# BUCK_CONVERTERS.net
KiCad netlist of a schematic drawn in Altium Designer
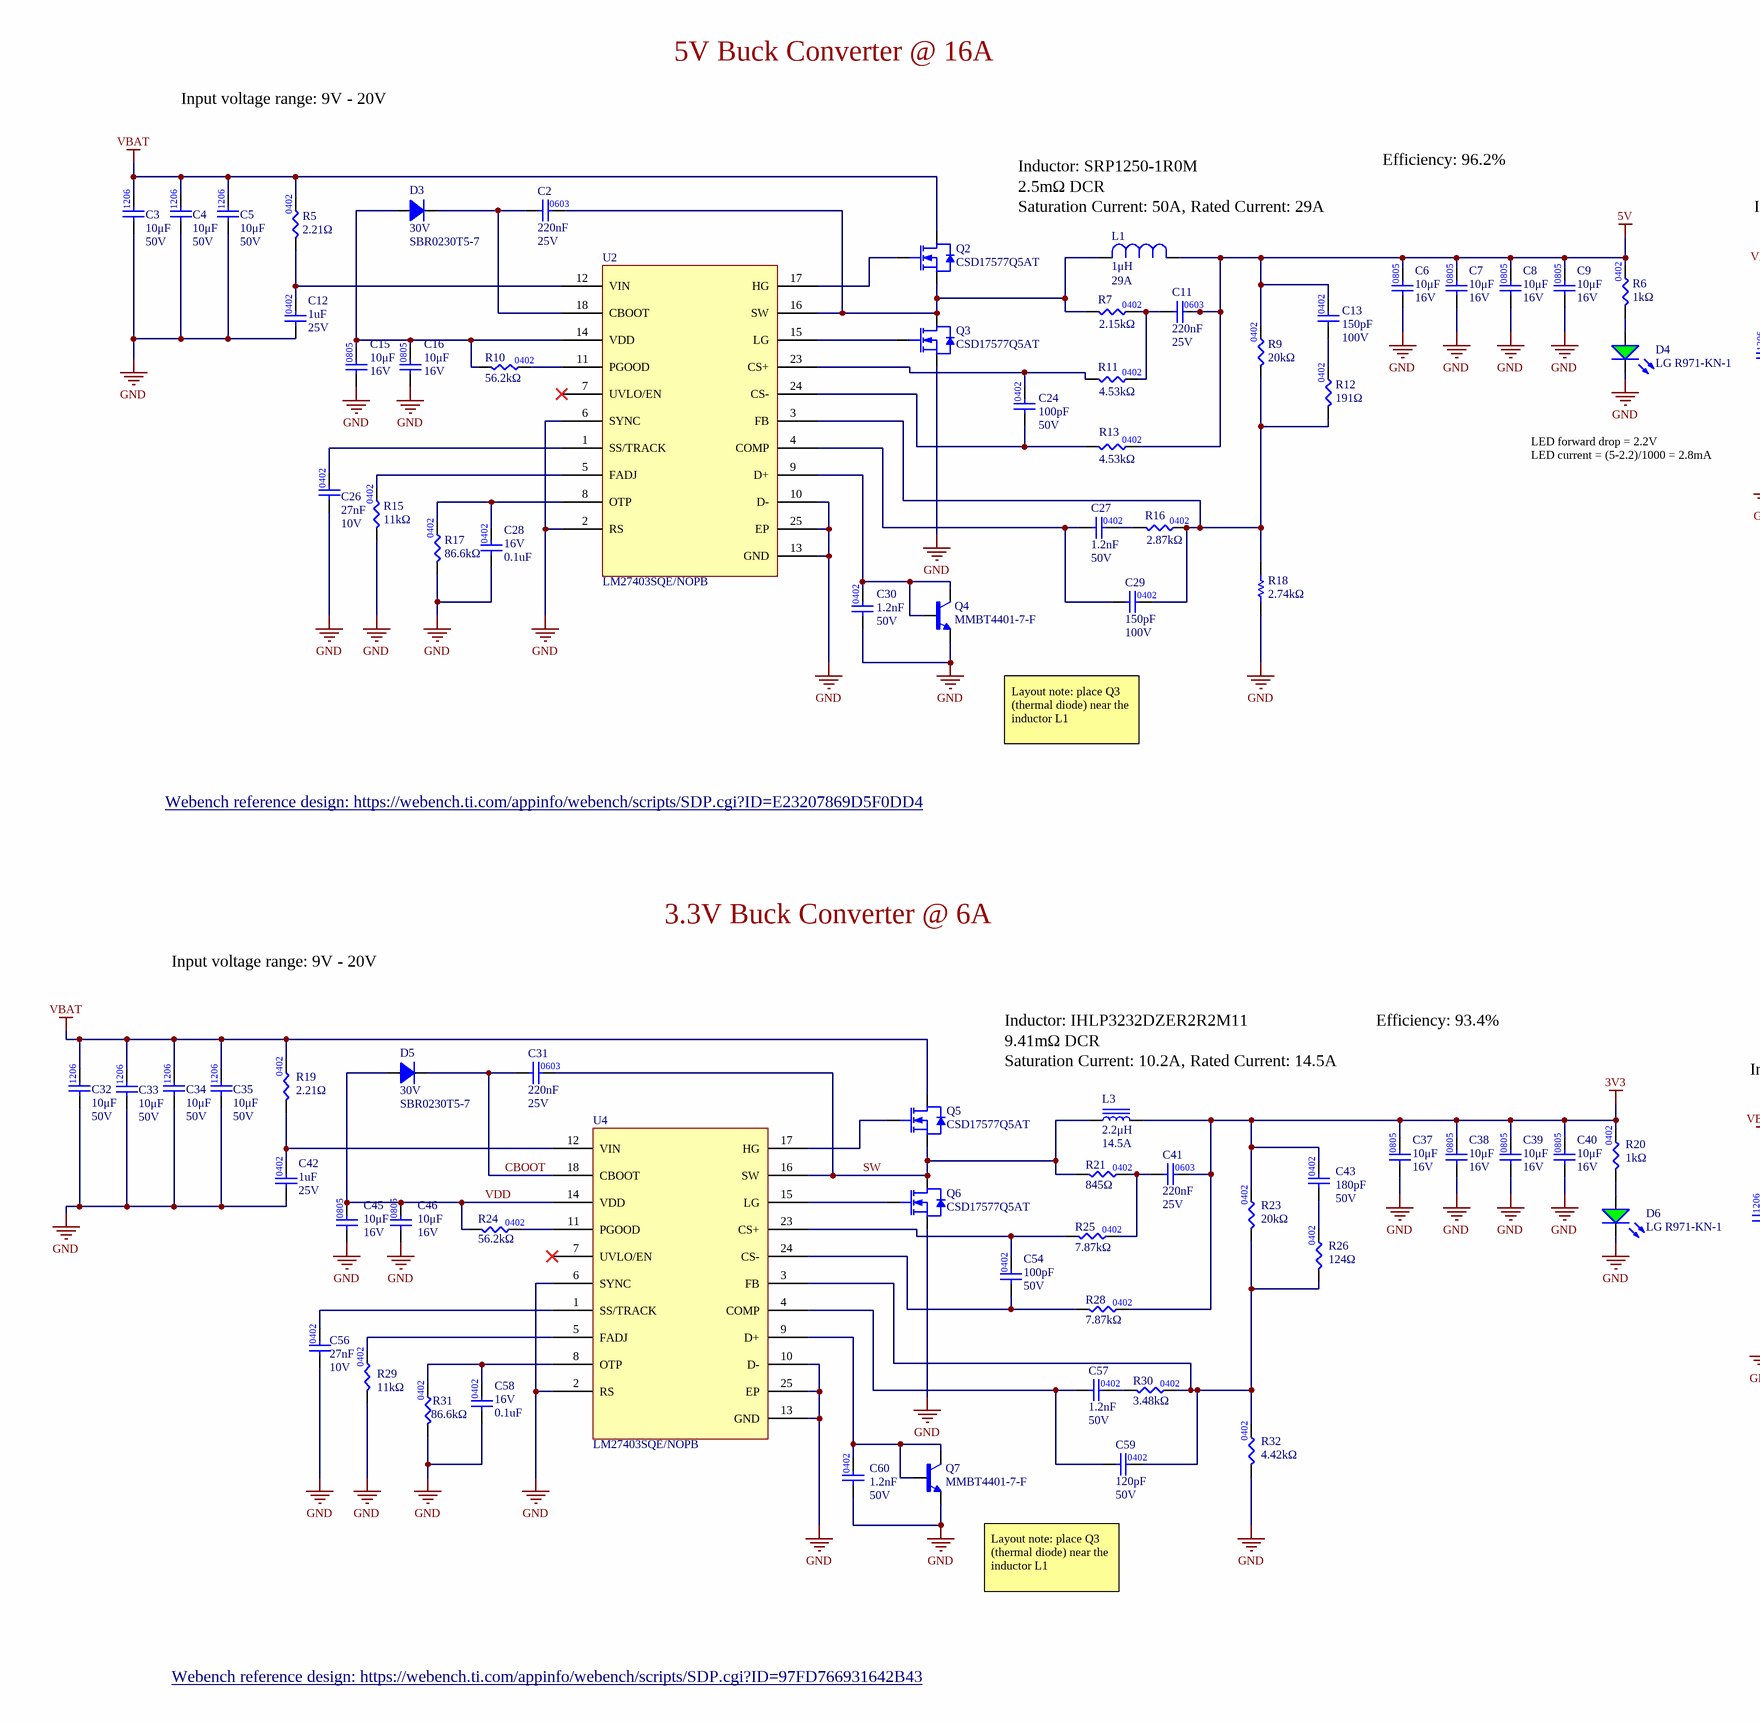
[diagram p0: BUCK CONVERTERS.SchDoc, left]
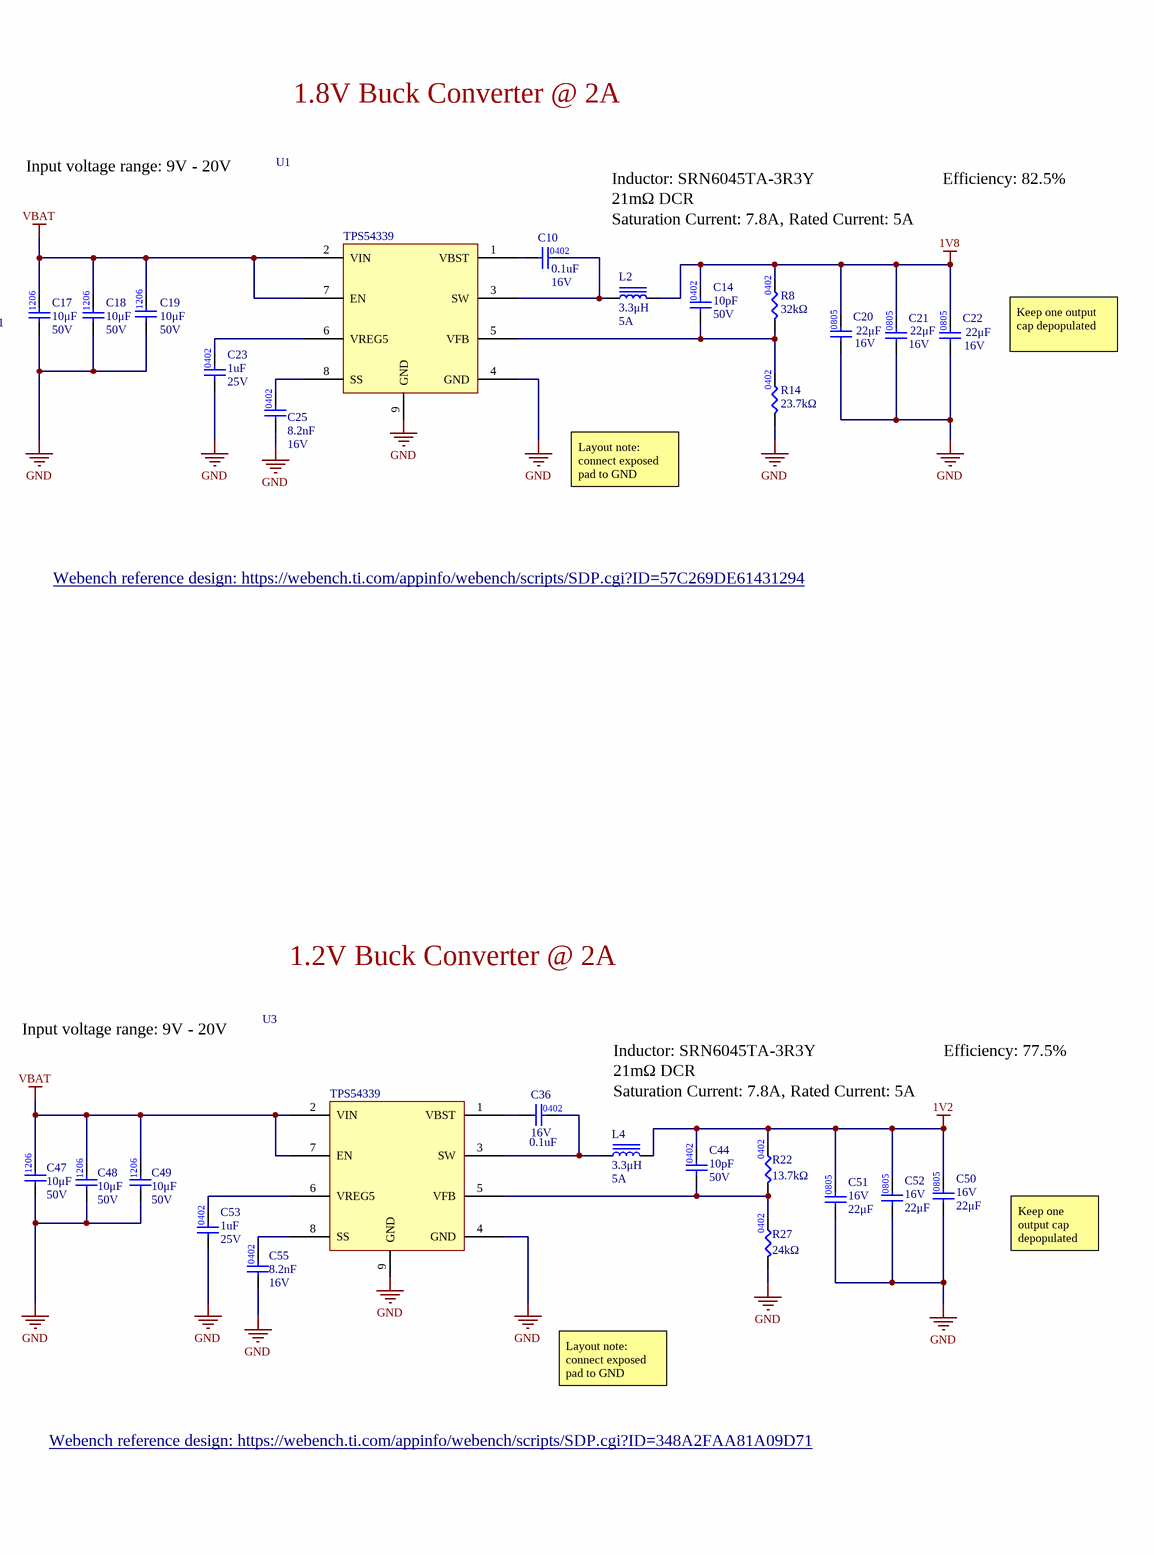
[diagram p1: BUCK CONVERTERS.SchDoc, right]

(export (version "E")
  (design (tool "Eeschema 10.0.6"))
  (components
    (comp (ref "C2")
      (value "CAP_0.22uF_25V_X5R_0402")
      (footprint "CAP0402")
      (description "0.22 µF ±10% 25V Ceramic Capacitor X5R 0402 (1005 Metric)")
      (fields
        (field (name "MANUFACTURER") "Yageo")
        (field (name "MANUFACTURER PART NUMBER") "CC0402KRX5R8BB224")
        (field (name "CAPACITANCE") "220nF")
        (field (name "RATED DC VOLTAGE (URDC)") "25V")
      )
      (libsource (lib "UWRT_Schematic_Library_2020") (part "CAP_0.22uF_25V_X5R_0402"))
    )
    (comp (ref "C3")
      (value "10μF")
      (footprint "CAP1210")
      (description "CAP CER 10UF 50V X7R 1210")
      (fields (field (name "VOLTAGE RATING") "50V") (field (name "Comment") "CAP_10uF_50V_1210"))
      (libsource (lib "UWRT_Schematic_Library_2020") (part "CAP_10uF_50V_1210"))
    )
    (comp (ref "C4")
      (value "10μF")
      (footprint "CAP1210")
      (description "CAP CER 10UF 50V X7R 1210")
      (fields (field (name "VOLTAGE RATING") "50V") (field (name "Comment") "CAP_10uF_50V_1210"))
      (libsource (lib "UWRT_Schematic_Library_2020") (part "CAP_10uF_50V_1210"))
    )
    (comp (ref "C5")
      (value "10μF")
      (footprint "CAP1210")
      (description "CAP CER 10UF 50V X7R 1210")
      (fields (field (name "VOLTAGE RATING") "50V") (field (name "Comment") "CAP_10uF_50V_1210"))
      (libsource (lib "UWRT_Schematic_Library_2020") (part "CAP_10uF_50V_1210"))
    )
    (comp (ref "C6")
      (value "10μF")
      (footprint "CAP2012")
      (description "CAP CER 10UF 16V X5R 0805")
      (fields (field (name "VOLTAGE RATING") "16V") (field (name "Comment") "CAP_10uF_16V_0805"))
      (libsource (lib "UWRT_Schematic_Library_2020") (part "CAP_10uF_16V_0805"))
    )
    (comp (ref "C7")
      (value "10μF")
      (footprint "CAP2012")
      (description "CAP CER 10UF 16V X5R 0805")
      (fields (field (name "VOLTAGE RATING") "16V") (field (name "Comment") "CAP_10uF_16V_0805"))
      (libsource (lib "UWRT_Schematic_Library_2020") (part "CAP_10uF_16V_0805"))
    )
    (comp (ref "C8")
      (value "10μF")
      (footprint "CAP2012")
      (description "CAP CER 10UF 16V X5R 0805")
      (fields (field (name "VOLTAGE RATING") "16V") (field (name "Comment") "CAP_10uF_16V_0805"))
      (libsource (lib "UWRT_Schematic_Library_2020") (part "CAP_10uF_16V_0805"))
    )
    (comp (ref "C9")
      (value "10μF")
      (footprint "CAP2012")
      (description "CAP CER 10UF 16V X5R 0805")
      (fields (field (name "VOLTAGE RATING") "16V") (field (name "Comment") "CAP_10uF_16V_0805"))
      (libsource (lib "UWRT_Schematic_Library_2020") (part "CAP_10uF_16V_0805"))
    )
    (comp (ref "C10")
      (value "CAP_0.1uF_16V_X7R_0402")
      (footprint "CAP0402")
      (description "Ceramic Capacitor, Ceramic")
      (fields
        (field (name "MANUFACTURER") "Taiyo Yuden")
        (field (name "MANUFACTURER PART NUMBER") "LMK212AC6106MD-T")
        (field (name "RATED DC VOLTAGE (URDC)") "16V")
        (field (name "CAPACITANCE") "0.1uF")
      )
      (libsource (lib "UWRT_Schematic_Library_2020") (part "CAP_0.1uF_16V_X7R_0402"))
    )
    (comp (ref "C11")
      (value "CAP_0.22uF_25V_X5R_0402")
      (footprint "CAP0402")
      (description "0.22 µF ±10% 25V Ceramic Capacitor X5R 0402 (1005 Metric)")
      (fields
        (field (name "MANUFACTURER") "Yageo")
        (field (name "MANUFACTURER PART NUMBER") "CC0402KRX5R8BB224")
        (field (name "CAPACITANCE") "220nF")
        (field (name "RATED DC VOLTAGE (URDC)") "25V")
      )
      (libsource (lib "UWRT_Schematic_Library_2020") (part "CAP_0.22uF_25V_X5R_0402"))
    )
    (comp (ref "C12")
      (value "CAP_1uF_25V_0402")
      (footprint "CAP0402")
      (description "±10% 25V Ceramic Capacitor X5R 0402 (1005 Metric)")
      (fields (field (name "CAPACITANCE") "1uF") (field (name "VOLTAGE") "25V"))
      (libsource (lib "UWRT_Schematic_Library_2020") (part "CAP_1uF_25V_0402"))
    )
    (comp (ref "C13")
      (value "CAP_150pF_100V_NP0_0402")
      (footprint "CAP0402")
      (description "±5% 100V Ceramic Capacitor C0G, NP0 0402 (1005 Metric)")
      (fields
        (field (name "MANUFACTURER") "Yageo")
        (field (name "MANUFACTURER PART NUMBER") "CGA2B2C0G2A151J050BE")
        (field (name "CAPACITANCE") "150pF")
        (field (name "RATED DC VOLTAGE (URDC)") "100V")
      )
      (libsource (lib "UWRT_Schematic_Library_2020") (part "CAP_150pF_100V_NP0_0402"))
    )
    (comp (ref "C14")
      (value "CAP_10pF_50V_0402")
      (footprint "CAP0402")
      (fields (field (name "CAPACITANCE") "10pF") (field (name "VOLTAGE") "50V"))
      (libsource (lib "UWRT_Schematic_Library_2020") (part "CAP_10pF_50V_0402"))
    )
    (comp (ref "C15")
      (value "10μF")
      (footprint "CAP2012")
      (description "CAP CER 10UF 16V X5R 0805")
      (fields (field (name "VOLTAGE RATING") "16V") (field (name "Comment") "CAP_10uF_16V_0805"))
      (libsource (lib "UWRT_Schematic_Library_2020") (part "CAP_10uF_16V_0805"))
    )
    (comp (ref "C16")
      (value "10μF")
      (footprint "CAP2012")
      (description "CAP CER 10UF 16V X5R 0805")
      (fields (field (name "VOLTAGE RATING") "16V") (field (name "Comment") "CAP_10uF_16V_0805"))
      (libsource (lib "UWRT_Schematic_Library_2020") (part "CAP_10uF_16V_0805"))
    )
    (comp (ref "C17")
      (value "10μF")
      (footprint "CAP1210")
      (description "CAP CER 10UF 50V X7R 1210")
      (fields (field (name "VOLTAGE RATING") "50V") (field (name "Comment") "CAP_10uF_50V_1210"))
      (libsource (lib "UWRT_Schematic_Library_2020") (part "CAP_10uF_50V_1210"))
    )
    (comp (ref "C18")
      (value "10μF")
      (footprint "CAP1210")
      (description "CAP CER 10UF 50V X7R 1210")
      (fields (field (name "VOLTAGE RATING") "50V") (field (name "Comment") "CAP_10uF_50V_1210"))
      (libsource (lib "UWRT_Schematic_Library_2020") (part "CAP_10uF_50V_1210"))
    )
    (comp (ref "C19")
      (value "10μF")
      (footprint "CAP1210")
      (description "CAP CER 10UF 50V X7R 1210")
      (fields (field (name "VOLTAGE RATING") "50V") (field (name "Comment") "CAP_10uF_50V_1210"))
      (libsource (lib "UWRT_Schematic_Library_2020") (part "CAP_10uF_50V_1210"))
    )
    (comp (ref "C20")
      (value "22μF")
      (footprint "CAP2012")
      (description "CAP CER 22UF 16V X5R 0805")
      (fields (field (name "VOLTAGE RATING") "16V") (field (name "Comment") "CAP_22uF_16V_0805"))
      (libsource (lib "UWRT_Schematic_Library_2020") (part "CAP_22uF_16V_0805"))
    )
    (comp (ref "C21")
      (value "22μF")
      (footprint "CAP2012")
      (description "CAP CER 22UF 16V X5R 0805")
      (fields (field (name "VOLTAGE RATING") "16V") (field (name "Comment") "CAP_22uF_16V_0805"))
      (libsource (lib "UWRT_Schematic_Library_2020") (part "CAP_22uF_16V_0805"))
    )
    (comp (ref "C22")
      (value "22μF")
      (footprint "CAP2012")
      (description "CAP CER 22UF 16V X5R 0805")
      (fields (field (name "VOLTAGE RATING") "16V") (field (name "Comment") "CAP_22uF_16V_0805"))
      (libsource (lib "UWRT_Schematic_Library_2020") (part "CAP_22uF_16V_0805"))
    )
    (comp (ref "C23")
      (value "CAP_1uF_25V_0402")
      (footprint "CAP0402")
      (description "±10% 25V Ceramic Capacitor X5R 0402 (1005 Metric)")
      (fields (field (name "CAPACITANCE") "1uF") (field (name "VOLTAGE") "25V"))
      (libsource (lib "UWRT_Schematic_Library_2020") (part "CAP_1uF_25V_0402"))
    )
    (comp (ref "C24")
      (value "CAP_100pF_50V_0402")
      (footprint "CAP0402")
      (description "100 pF ±10% 50V Ceramic Capacitor X7R 0402 (1005 Metric)")
      (fields (field (name "CAPACITANCE") "100pF") (field (name "VOLTAGE") "50V"))
      (libsource (lib "UWRT_Schematic_Library_2020") (part "CAP_100pF_50V_0402"))
    )
    (comp (ref "C25")
      (value "CAP_8.2nF_16V_0402")
      (footprint "CAP0402")
      (description "8200 pF ±10% 16V Ceramic Capacitor X7R 0402 (1005 Metric)")
      (fields (field (name "CAPACITANCE") "8.2nF") (field (name "VOLTAGE") "16V"))
      (libsource (lib "UWRT_Schematic_Library_2020") (part "CAP_8.2nF_16V_0402"))
    )
    (comp (ref "C26")
      (value "CAP_0.027uF_10V_X7R_0402")
      (footprint "CAP0402")
      (description "0.027 µF ±10% 10V Ceramic Capacitor X7R 0402 (1005 Metric)")
      (fields
        (field (name "MANUFACTURER") "Yageo")
        (field (name "MANUFACTURER PART NUMBER") "CC0402KRX7R6BB273")
        (field (name "CAPACITANCE") "27nF")
        (field (name "RATED DC VOLTAGE (URDC)") "10V")
      )
      (libsource (lib "UWRT_Schematic_Library_2020") (part "CAP_0.027uF_10V_X7R_0402"))
    )
    (comp (ref "C27")
      (value "CAP_1.2nF_50V_X7R_0402")
      (footprint "CAP0402")
      (description "1200 pF ±5% 50V Ceramic Capacitor X7R 0402 (1005 Metric)")
      (fields
        (field (name "MANUFACTURER") "Yageo")
        (field (name "MANUFACTURER PART NUMBER") "CC0402JRX7R9BB122")
        (field (name "CAPACITANCE") "1.2nF")
        (field (name "RATED DC VOLTAGE (URDC)") "50V")
      )
      (libsource (lib "UWRT_Schematic_Library_2020") (part "CAP_1.2nF_50V_X7R_0402"))
    )
    (comp (ref "C28")
      (value "CAP_0.1uF_16V_X7R_0402")
      (footprint "CAP0402")
      (description "Ceramic Capacitor, Ceramic")
      (fields
        (field (name "MANUFACTURER") "Taiyo Yuden")
        (field (name "MANUFACTURER PART NUMBER") "LMK212AC6106MD-T")
        (field (name "RATED DC VOLTAGE (URDC)") "16V")
        (field (name "CAPACITANCE") "0.1uF")
      )
      (libsource (lib "UWRT_Schematic_Library_2020") (part "CAP_0.1uF_16V_X7R_0402"))
    )
    (comp (ref "C29")
      (value "CAP_150pF_100V_NP0_0402")
      (footprint "CAP0402")
      (description "±5% 100V Ceramic Capacitor C0G, NP0 0402 (1005 Metric)")
      (fields
        (field (name "MANUFACTURER") "Yageo")
        (field (name "MANUFACTURER PART NUMBER") "CGA2B2C0G2A151J050BE")
        (field (name "CAPACITANCE") "150pF")
        (field (name "RATED DC VOLTAGE (URDC)") "100V")
      )
      (libsource (lib "UWRT_Schematic_Library_2020") (part "CAP_150pF_100V_NP0_0402"))
    )
    (comp (ref "C30")
      (value "CAP_1.2nF_50V_X7R_0402")
      (footprint "CAP0402")
      (description "1200 pF ±5% 50V Ceramic Capacitor X7R 0402 (1005 Metric)")
      (fields
        (field (name "MANUFACTURER") "Yageo")
        (field (name "MANUFACTURER PART NUMBER") "CC0402JRX7R9BB122")
        (field (name "CAPACITANCE") "1.2nF")
        (field (name "RATED DC VOLTAGE (URDC)") "50V")
      )
      (libsource (lib "UWRT_Schematic_Library_2020") (part "CAP_1.2nF_50V_X7R_0402"))
    )
    (comp (ref "C31")
      (value "CAP_0.22uF_25V_X5R_0402")
      (footprint "CAP0402")
      (description "0.22 µF ±10% 25V Ceramic Capacitor X5R 0402 (1005 Metric)")
      (fields
        (field (name "MANUFACTURER") "Yageo")
        (field (name "MANUFACTURER PART NUMBER") "CC0402KRX5R8BB224")
        (field (name "CAPACITANCE") "220nF")
        (field (name "RATED DC VOLTAGE (URDC)") "25V")
      )
      (libsource (lib "UWRT_Schematic_Library_2020") (part "CAP_0.22uF_25V_X5R_0402"))
    )
    (comp (ref "C32")
      (value "10μF")
      (footprint "CAP1210")
      (description "CAP CER 10UF 50V X7R 1210")
      (fields (field (name "VOLTAGE RATING") "50V") (field (name "Comment") "CAP_10uF_50V_1210"))
      (libsource (lib "UWRT_Schematic_Library_2020") (part "CAP_10uF_50V_1210"))
    )
    (comp (ref "C33")
      (value "10μF")
      (footprint "CAP1210")
      (description "CAP CER 10UF 50V X7R 1210")
      (fields (field (name "VOLTAGE RATING") "50V") (field (name "Comment") "CAP_10uF_50V_1210"))
      (libsource (lib "UWRT_Schematic_Library_2020") (part "CAP_10uF_50V_1210"))
    )
    (comp (ref "C34")
      (value "10μF")
      (footprint "CAP1210")
      (description "CAP CER 10UF 50V X7R 1210")
      (fields (field (name "VOLTAGE RATING") "50V") (field (name "Comment") "CAP_10uF_50V_1210"))
      (libsource (lib "UWRT_Schematic_Library_2020") (part "CAP_10uF_50V_1210"))
    )
    (comp (ref "C35")
      (value "10μF")
      (footprint "CAP0805")
      (description "CAP CER 10UF 50V X7R 1210")
      (fields (field (name "VOLTAGE RATING") "50V") (field (name "Comment") "CAP_10uF_50V_1210"))
      (libsource (lib "UWRT_Schematic_Library_2020") (part "CAP_10uF_50V_1210"))
    )
    (comp (ref "C36")
      (value "CAP_0.1uF_16V_X7R_0402")
      (footprint "CAP0402")
      (description "Ceramic Capacitor, Ceramic")
      (fields
        (field (name "MANUFACTURER") "Taiyo Yuden")
        (field (name "MANUFACTURER PART NUMBER") "LMK212AC6106MD-T")
        (field (name "RATED DC VOLTAGE (URDC)") "16V")
        (field (name "CAPACITANCE") "0.1uF")
      )
      (libsource (lib "UWRT_Schematic_Library_2020") (part "CAP_0.1uF_16V_X7R_0402"))
    )
    (comp (ref "C37")
      (value "10μF")
      (footprint "CAP2012")
      (description "CAP CER 10UF 16V X5R 0805")
      (fields (field (name "VOLTAGE RATING") "16V") (field (name "Comment") "CAP_10uF_16V_0805"))
      (libsource (lib "UWRT_Schematic_Library_2020") (part "CAP_10uF_16V_0805"))
    )
    (comp (ref "C38")
      (value "10μF")
      (footprint "CAP2012")
      (description "CAP CER 10UF 16V X5R 0805")
      (fields (field (name "VOLTAGE RATING") "16V") (field (name "Comment") "CAP_10uF_16V_0805"))
      (libsource (lib "UWRT_Schematic_Library_2020") (part "CAP_10uF_16V_0805"))
    )
    (comp (ref "C39")
      (value "10μF")
      (footprint "CAP2012")
      (description "CAP CER 10UF 16V X5R 0805")
      (fields (field (name "VOLTAGE RATING") "16V") (field (name "Comment") "CAP_10uF_16V_0805"))
      (libsource (lib "UWRT_Schematic_Library_2020") (part "CAP_10uF_16V_0805"))
    )
    (comp (ref "C40")
      (value "10μF")
      (footprint "CAP2012")
      (description "CAP CER 10UF 16V X5R 0805")
      (fields (field (name "VOLTAGE RATING") "16V") (field (name "Comment") "CAP_10uF_16V_0805"))
      (libsource (lib "UWRT_Schematic_Library_2020") (part "CAP_10uF_16V_0805"))
    )
    (comp (ref "C41")
      (value "CAP_0.22uF_25V_X5R_0402")
      (footprint "CAP0402")
      (description "0.22 µF ±10% 25V Ceramic Capacitor X5R 0402 (1005 Metric)")
      (fields
        (field (name "MANUFACTURER") "Yageo")
        (field (name "MANUFACTURER PART NUMBER") "CC0402KRX5R8BB224")
        (field (name "CAPACITANCE") "220nF")
        (field (name "RATED DC VOLTAGE (URDC)") "25V")
      )
      (libsource (lib "UWRT_Schematic_Library_2020") (part "CAP_0.22uF_25V_X5R_0402"))
    )
    (comp (ref "C42")
      (value "CAP_1uF_25V_0402")
      (footprint "CAP0402")
      (description "±10% 25V Ceramic Capacitor X5R 0402 (1005 Metric)")
      (fields (field (name "CAPACITANCE") "1uF") (field (name "VOLTAGE") "25V"))
      (libsource (lib "UWRT_Schematic_Library_2020") (part "CAP_1uF_25V_0402"))
    )
    (comp (ref "C43")
      (value "CAP_180pF_50V_0402")
      (footprint "CAP0402")
      (description "180 pF ±10% 50V Ceramic Capacitor X7R 0402 (1005 Metric)")
      (fields (field (name "CAPACITANCE") "180pF") (field (name "VOLTAGE") "50V"))
      (libsource (lib "UWRT_Schematic_Library_2020") (part "CAP_180pF_50V_0402"))
    )
    (comp (ref "C44")
      (value "CAP_10pF_50V_0402")
      (footprint "CAP0402")
      (fields (field (name "CAPACITANCE") "10pF") (field (name "VOLTAGE") "50V"))
      (libsource (lib "UWRT_Schematic_Library_2020") (part "CAP_10pF_50V_0402"))
    )
    (comp (ref "C45")
      (value "10μF")
      (footprint "CAP2012")
      (description "CAP CER 10UF 16V X5R 0805")
      (fields (field (name "VOLTAGE RATING") "16V") (field (name "Comment") "CAP_10uF_16V_0805"))
      (libsource (lib "UWRT_Schematic_Library_2020") (part "CAP_10uF_16V_0805"))
    )
    (comp (ref "C46")
      (value "10μF")
      (footprint "CAP2012")
      (description "CAP CER 10UF 16V X5R 0805")
      (fields (field (name "VOLTAGE RATING") "16V") (field (name "Comment") "CAP_10uF_16V_0805"))
      (libsource (lib "UWRT_Schematic_Library_2020") (part "CAP_10uF_16V_0805"))
    )
    (comp (ref "C47")
      (value "10μF")
      (footprint "CAP1210")
      (description "CAP CER 10UF 50V X7R 1210")
      (fields (field (name "VOLTAGE RATING") "50V") (field (name "Comment") "CAP_10uF_50V_1210"))
      (libsource (lib "UWRT_Schematic_Library_2020") (part "CAP_10uF_50V_1210"))
    )
    (comp (ref "C48")
      (value "10μF")
      (footprint "CAP1210")
      (description "CAP CER 10UF 50V X7R 1210")
      (fields (field (name "VOLTAGE RATING") "50V") (field (name "Comment") "CAP_10uF_50V_1210"))
      (libsource (lib "UWRT_Schematic_Library_2020") (part "CAP_10uF_50V_1210"))
    )
    (comp (ref "C49")
      (value "10μF")
      (footprint "CAP1210")
      (description "CAP CER 10UF 50V X7R 1210")
      (fields (field (name "VOLTAGE RATING") "50V") (field (name "Comment") "CAP_10uF_50V_1210"))
      (libsource (lib "UWRT_Schematic_Library_2020") (part "CAP_10uF_50V_1210"))
    )
    (comp (ref "C50")
      (value "22μF")
      (footprint "CAP2012")
      (description "CAP CER 22UF 16V X5R 0805")
      (fields (field (name "VOLTAGE RATING") "16V") (field (name "Comment") "CAP_22uF_16V_0805"))
      (libsource (lib "UWRT_Schematic_Library_2020") (part "CAP_22uF_16V_0805"))
    )
    (comp (ref "C51")
      (value "22μF")
      (footprint "CAP2012")
      (description "CAP CER 22UF 16V X5R 0805")
      (fields (field (name "VOLTAGE RATING") "16V") (field (name "Comment") "CAP_22uF_16V_0805"))
      (libsource (lib "UWRT_Schematic_Library_2020") (part "CAP_22uF_16V_0805"))
    )
    (comp (ref "C52")
      (value "22μF")
      (footprint "CAP2012")
      (description "CAP CER 22UF 16V X5R 0805")
      (fields (field (name "VOLTAGE RATING") "16V") (field (name "Comment") "CAP_22uF_16V_0805"))
      (libsource (lib "UWRT_Schematic_Library_2020") (part "CAP_22uF_16V_0805"))
    )
    (comp (ref "C53")
      (value "CAP_1uF_25V_0402")
      (footprint "CAP0402")
      (description "±10% 25V Ceramic Capacitor X5R 0402 (1005 Metric)")
      (fields (field (name "CAPACITANCE") "1uF") (field (name "VOLTAGE") "25V"))
      (libsource (lib "UWRT_Schematic_Library_2020") (part "CAP_1uF_25V_0402"))
    )
    (comp (ref "C54")
      (value "CAP_100pF_50V_0402")
      (footprint "CAP0402")
      (description "100 pF ±10% 50V Ceramic Capacitor X7R 0402 (1005 Metric)")
      (fields (field (name "CAPACITANCE") "100pF") (field (name "VOLTAGE") "50V"))
      (libsource (lib "UWRT_Schematic_Library_2020") (part "CAP_100pF_50V_0402"))
    )
    (comp (ref "C55")
      (value "CAP_8.2nF_16V_0402")
      (footprint "CAP0402")
      (description "8200 pF ±10% 16V Ceramic Capacitor X7R 0402 (1005 Metric)")
      (fields (field (name "CAPACITANCE") "8.2nF") (field (name "VOLTAGE") "16V"))
      (libsource (lib "UWRT_Schematic_Library_2020") (part "CAP_8.2nF_16V_0402"))
    )
    (comp (ref "C56")
      (value "CAP_0.027uF_10V_X7R_0402")
      (footprint "CAP0402")
      (description "0.027 µF ±10% 10V Ceramic Capacitor X7R 0402 (1005 Metric)")
      (fields
        (field (name "MANUFACTURER") "Yageo")
        (field (name "MANUFACTURER PART NUMBER") "CC0402KRX7R6BB273")
        (field (name "CAPACITANCE") "27nF")
        (field (name "RATED DC VOLTAGE (URDC)") "10V")
      )
      (libsource (lib "UWRT_Schematic_Library_2020") (part "CAP_0.027uF_10V_X7R_0402"))
    )
    (comp (ref "C57")
      (value "CAP_1.2nF_50V_X7R_0402")
      (footprint "CAP0402")
      (description "1200 pF ±5% 50V Ceramic Capacitor X7R 0402 (1005 Metric)")
      (fields
        (field (name "MANUFACTURER") "Yageo")
        (field (name "MANUFACTURER PART NUMBER") "CC0402JRX7R9BB122")
        (field (name "CAPACITANCE") "1.2nF")
        (field (name "RATED DC VOLTAGE (URDC)") "50V")
      )
      (libsource (lib "UWRT_Schematic_Library_2020") (part "CAP_1.2nF_50V_X7R_0402"))
    )
    (comp (ref "C58")
      (value "CAP_0.1uF_16V_X7R_0402")
      (footprint "CAP0402")
      (description "Ceramic Capacitor, Ceramic")
      (fields
        (field (name "MANUFACTURER") "Taiyo Yuden")
        (field (name "MANUFACTURER PART NUMBER") "LMK212AC6106MD-T")
        (field (name "RATED DC VOLTAGE (URDC)") "16V")
        (field (name "CAPACITANCE") "0.1uF")
      )
      (libsource (lib "UWRT_Schematic_Library_2020") (part "CAP_0.1uF_16V_X7R_0402"))
    )
    (comp (ref "C59")
      (value "CAP_120pF_50V_0402")
      (footprint "CAP0402")
      (description "120 pF ±10% 50V Ceramic Capacitor X7R 0402 (1005 Metric)")
      (fields (field (name "CAPACITANCE") "120pF") (field (name "VOLTAGE") "50V"))
      (libsource (lib "UWRT_Schematic_Library_2020") (part "CAP_120pF_50V_0402"))
    )
    (comp (ref "C60")
      (value "CAP_1.2nF_50V_X7R_0402")
      (footprint "CAP0402")
      (description "1200 pF ±5% 50V Ceramic Capacitor X7R 0402 (1005 Metric)")
      (fields
        (field (name "MANUFACTURER") "Yageo")
        (field (name "MANUFACTURER PART NUMBER") "CC0402JRX7R9BB122")
        (field (name "CAPACITANCE") "1.2nF")
        (field (name "RATED DC VOLTAGE (URDC)") "50V")
      )
      (libsource (lib "UWRT_Schematic_Library_2020") (part "CAP_1.2nF_50V_X7R_0402"))
    )
    (comp (ref "D3")
      (value "30V")
      (footprint "SOD523")
      (description "Diode Super Barrier 30 V 200mA Surface Mount SOD-523")
      (fields
        (field (name "MANUFACTURER PART NUMBER 1") "SBR0230T5-7")
        (field (name "Comment") "SBR0230T5-7")
      )
      (libsource (lib "UWRT_Schematic_Library_2020") (part "DIO_30V_200mA"))
    )
    (comp (ref "D4")
      (value "DIO_LED_G")
      (footprint "LED_0805_GREEN")
      (description "LED GREEN DIFFUSED 0805 SMD")
      (fields (field (name "MANUFACTURER PART NUMBER 1") "LG R971-KN-1"))
      (libsource (lib "UWRT_Schematic_Library_2020") (part "DIO_LED_G"))
    )
    (comp (ref "D5")
      (value "30V")
      (footprint "SOD523")
      (description "Diode Super Barrier 30 V 200mA Surface Mount SOD-523")
      (fields
        (field (name "MANUFACTURER PART NUMBER 1") "SBR0230T5-7")
        (field (name "Comment") "SBR0230T5-7")
      )
      (libsource (lib "UWRT_Schematic_Library_2020") (part "DIO_30V_200mA"))
    )
    (comp (ref "D6")
      (value "DIO_LED_G")
      (footprint "LED_0805_GREEN")
      (description "LED GREEN DIFFUSED 0805 SMD")
      (fields (field (name "MANUFACTURER PART NUMBER 1") "LG R971-KN-1"))
      (libsource (lib "UWRT_Schematic_Library_2020") (part "DIO_LED_G"))
    )
    (comp (ref "L1")
      (value "IND_1uH_29A")
      (footprint "IND_BOURNS_SRP1250")
      (description "FIXED IND 1UH 29A 2.5 MOHM SMD")
      (fields (field (name "CURRENT RATING") "29A") (field (name "INDUCTANCE") "1μH"))
      (libsource (lib "UWRT_Schematic_Library_2020") (part "IND_1uH_29A"))
    )
    (comp (ref "L2")
      (value "IND_3.3uH_5A")
      (footprint "IND_SRN6045TA-3R3Y")
      (description "FIXED IND 3.3UH 5A 21 MOHM SMD")
      (fields (field (name "CURRENT RATING") "5A") (field (name "INDUCTANCE") "3.3μH"))
      (libsource (lib "UWRT_Schematic_Library_2020") (part "IND_3.3uH_5A"))
    )
    (comp (ref "L3")
      (value "IND_2.2uH_14.5A")
      (footprint "IND_VISHAY_IHLP3232DZER2R2M11")
      (description "INDUCTOR 2.2UH 14.5A 9.41 MOHM")
      (fields (field (name "CURRENT RATING") "14.5A") (field (name "INDUCTANCE") "2.2μH"))
      (libsource (lib "UWRT_Schematic_Library_2020") (part "IND_2.2uH_14.5A"))
    )
    (comp (ref "L4")
      (value "IND_3.3uH_5A")
      (footprint "IND_SRN6045TA-3R3Y")
      (description "FIXED IND 3.3UH 5A 21 MOHM SMD")
      (fields (field (name "CURRENT RATING") "5A") (field (name "INDUCTANCE") "3.3μH"))
      (libsource (lib "UWRT_Schematic_Library_2020") (part "IND_3.3uH_5A"))
    )
    (comp (ref "Q2")
      (value "NMOS_30V_60A")
      (footprint "MOSFET_CSD19531Q5A")
      (description "MOSFET N-CH 30V 60A 8VSON")
      (fields (field (name "MANUFACTURER PART NUMBER 1") "CSD17577Q5AT"))
      (libsource (lib "UWRT_Schematic_Library_2020") (part "NMOS_30V_60A"))
    )
    (comp (ref "Q3")
      (value "NMOS_30V_60A")
      (footprint "MOSFET_CSD19531Q5A")
      (description "MOSFET N-CH 30V 60A 8VSON")
      (fields (field (name "MANUFACTURER PART NUMBER 1") "CSD17577Q5AT"))
      (libsource (lib "UWRT_Schematic_Library_2020") (part "NMOS_30V_60A"))
    )
    (comp (ref "Q4")
      (value "MMBT4401-7-F")
      (footprint "MMBT4401-7-F")
      (description "Bipolar (BJT) Transistor NPN 40 V 600 mA 250MHz 310 mW Surface Mount SOT-23-3")
      (libsource (lib "UWRT_Schematic_Library_2020") (part "MMBT4401-7-F"))
    )
    (comp (ref "Q5")
      (value "NMOS_30V_60A")
      (footprint "MOSFET_CSD19531Q5A")
      (description "MOSFET N-CH 30V 60A 8VSON")
      (fields (field (name "MANUFACTURER PART NUMBER 1") "CSD17577Q5AT"))
      (libsource (lib "UWRT_Schematic_Library_2020") (part "NMOS_30V_60A"))
    )
    (comp (ref "Q6")
      (value "NMOS_30V_60A")
      (footprint "MOSFET_CSD19531Q5A")
      (description "MOSFET N-CH 30V 60A 8VSON")
      (fields (field (name "MANUFACTURER PART NUMBER 1") "CSD17577Q5AT"))
      (libsource (lib "UWRT_Schematic_Library_2020") (part "NMOS_30V_60A"))
    )
    (comp (ref "Q7")
      (value "MMBT4401-7-F")
      (footprint "MMBT4401-7-F")
      (description "Bipolar (BJT) Transistor NPN 40 V 600 mA 250MHz 310 mW Surface Mount SOT-23-3")
      (libsource (lib "UWRT_Schematic_Library_2020") (part "MMBT4401-7-F"))
    )
    (comp (ref "R5")
      (value "2.21Ω")
      (footprint "RES0402")
      (description "RES 2.21 OHM 1% 1/16W 0402")
      (fields (field (name "POWER") "0.063W, 1/16W") (field (name "TOLERANCE") "1%"))
      (libsource (lib "UWRT_Schematic_Library_2020") (part "RES_2.21Ω_0402_1%"))
    )
    (comp (ref "R6")
      (value "RES_1kΩ_0402")
      (footprint "RES0402")
      (fields
        (field (name "MANUFACTURER") "Stackpole Electronics")
        (field (name "MANUFACTURER PART NUMBER") "RMCF0402FT1K00")
        (field (name "TOLERANCE") "1%")
        (field (name "RESISTANCE") "1kΩ")
      )
      (libsource (lib "UWRT_Schematic_Library_2020") (part "RES_1kΩ_0402"))
    )
    (comp (ref "R7")
      (value "2.15kΩ")
      (footprint "RES0402")
      (description "RES SMD 2.15K OHM 1% 1/16W 0402")
      (fields (field (name "POWER") "0.063W, 1/16W") (field (name "TOLERANCE") "1%"))
      (libsource (lib "UWRT_Schematic_Library_2020") (part "RES_2.15kΩ_0402_1%"))
    )
    (comp (ref "R8")
      (value "32kΩ")
      (footprint "RES0402")
      (description "RES 32K OHM 1% 1/16W 0402")
      (fields (field (name "TOLERANCE") "1%") (field (name "Comment") "RES_32kΩ_0402_1%"))
      (libsource (lib "UWRT_Schematic_Library_2020") (part "RES_32kΩ_0402_1%"))
    )
    (comp (ref "R9")
      (value "20kΩ")
      (footprint "RES0402")
      (description "RES SMD 20K OHM 1% 1/16W 0402")
      (fields (field (name "POWER") "0.063W, 1/16W") (field (name "TOLERANCE") "1%"))
      (libsource (lib "UWRT_Schematic_Library_2020") (part "RES_20kΩ_0402_1%"))
    )
    (comp (ref "R10")
      (value "56.2kΩ")
      (footprint "RES0402")
      (description "RES SMD 56.2K OHM 1% 1/16W 0402")
      (fields (field (name "POWER") "0.063W, 1/16W") (field (name "TOLERANCE") "1%"))
      (libsource (lib "UWRT_Schematic_Library_2020") (part "RES_56.2kΩ_0402_1%"))
    )
    (comp (ref "R11")
      (value "4.53kΩ")
      (footprint "RES0402")
      (description "RES SMD 4.53K OHM 1% 1/16W 0402")
      (fields (field (name "TOLERANCE") "1%") (field (name "Comment") "RES_4.53kΩ_0402_1%"))
      (libsource (lib "UWRT_Schematic_Library_2020") (part "RES_4.53kΩ_0402_1%"))
    )
    (comp (ref "R12")
      (value "191Ω")
      (footprint "RES0402")
      (description "RES SMD 191 OHM 1% 1/16W 0402")
      (fields (field (name "POWER") "0.063W, 1/16W") (field (name "TOLERANCE") "1%"))
      (libsource (lib "UWRT_Schematic_Library_2020") (part "RES_191Ω_0402_1%"))
    )
    (comp (ref "R13")
      (value "4.53kΩ")
      (footprint "RES0402")
      (description "RES SMD 4.53K OHM 1% 1/16W 0402")
      (fields (field (name "TOLERANCE") "1%") (field (name "Comment") "RES_4.53kΩ_0402_1%"))
      (libsource (lib "UWRT_Schematic_Library_2020") (part "RES_4.53kΩ_0402_1%"))
    )
    (comp (ref "R14")
      (value "23.7kΩ")
      (footprint "RES0402")
      (description "RES 23.7K OHM 1% 1/16W 0402")
      (fields (field (name "POWER") "0.063W, 1/16W") (field (name "TOLERANCE") "1%"))
      (libsource (lib "UWRT_Schematic_Library_2020") (part "RES_23.7kΩ_0402_1%"))
    )
    (comp (ref "R15")
      (value "11kΩ")
      (footprint "RES0402")
      (description "RES 11K OHM 1% 1/16W 0402")
      (fields (field (name "POWER") "0.063W, 1/16W") (field (name "TOLERANCE") "1%"))
      (libsource (lib "UWRT_Schematic_Library_2020") (part "RES_11kΩ_0402_1%"))
    )
    (comp (ref "R16")
      (value "2.87kΩ")
      (footprint "RES0402")
      (description "RES SMD 2.87K OHM 1% 1/16W 0402")
      (fields (field (name "TOLERANCE") "1%") (field (name "Comment") "RES_2.87kΩ_0402_1%"))
      (libsource (lib "UWRT_Schematic_Library_2020") (part "RES_2.87kΩ_0402_1%"))
    )
    (comp (ref "R17")
      (value "86.6kΩ")
      (footprint "RES0402")
      (description "RES SMD 86.6K OHM 1% 1/16W 0402")
      (fields (field (name "POWER") "0.063W, 1/16W") (field (name "TOLERANCE") "1%"))
      (libsource (lib "UWRT_Schematic_Library_2020") (part "RES_86.6kΩ_0402_1%"))
    )
    (comp (ref "R18")
      (value "2.74kΩ")
      (footprint "RES0402")
      (description "RES 2.74K OHM 1% 1/16W 0402")
      (fields (field (name "POWER") "0.063W, 1/16W") (field (name "TOLERANCE") "1%"))
      (libsource (lib "UWRT_Schematic_Library_2020") (part "RES_2.74kΩ_0402_1%"))
    )
    (comp (ref "R19")
      (value "2.21Ω")
      (footprint "RES0402")
      (description "RES 2.21 OHM 1% 1/16W 0402")
      (fields (field (name "POWER") "0.063W, 1/16W") (field (name "TOLERANCE") "1%"))
      (libsource (lib "UWRT_Schematic_Library_2020") (part "RES_2.21Ω_0402_1%"))
    )
    (comp (ref "R20")
      (value "RES_1kΩ_0402")
      (footprint "RES0402")
      (fields
        (field (name "MANUFACTURER") "Stackpole Electronics")
        (field (name "MANUFACTURER PART NUMBER") "RMCF0402FT1K00")
        (field (name "TOLERANCE") "1%")
        (field (name "RESISTANCE") "1kΩ")
      )
      (libsource (lib "UWRT_Schematic_Library_2020") (part "RES_1kΩ_0402"))
    )
    (comp (ref "R21")
      (value "845Ω")
      (footprint "RES0402")
      (description "RES SMD 845 OHM 1% 1/16W 0402")
      (fields (field (name "POWER") "0.063W, 1/16W") (field (name "TOLERANCE") "1%"))
      (libsource (lib "UWRT_Schematic_Library_2020") (part "RES_845Ω_0402_1%"))
    )
    (comp (ref "R22")
      (value "13.7kΩ")
      (footprint "RES0402")
      (description "RES SMD 13.7K OHM 1% 1/16W 0402")
      (fields (field (name "POWER") "0.063W, 1/16W") (field (name "TOLERANCE") "1%"))
      (libsource (lib "UWRT_Schematic_Library_2020") (part "RES_13.7kΩ_0402_1%"))
    )
    (comp (ref "R23")
      (value "20kΩ")
      (footprint "RES0402")
      (description "RES SMD 20K OHM 1% 1/16W 0402")
      (fields (field (name "POWER") "0.063W, 1/16W") (field (name "TOLERANCE") "1%"))
      (libsource (lib "UWRT_Schematic_Library_2020") (part "RES_20kΩ_0402_1%"))
    )
    (comp (ref "R24")
      (value "56.2kΩ")
      (footprint "RES0402")
      (description "RES SMD 56.2K OHM 1% 1/16W 0402")
      (fields (field (name "POWER") "0.063W, 1/16W") (field (name "TOLERANCE") "1%"))
      (libsource (lib "UWRT_Schematic_Library_2020") (part "RES_56.2kΩ_0402_1%"))
    )
    (comp (ref "R25")
      (value "7.87kΩ")
      (footprint "RES0402")
      (description "RES 7.87K OHM 1% 1/16W 0402")
      (fields (field (name "POWER") "0.063W, 1/16W") (field (name "TOLERANCE") "1%"))
      (libsource (lib "UWRT_Schematic_Library_2020") (part "RES_7.87kΩ_0402_1%"))
    )
    (comp (ref "R26")
      (value "124Ω")
      (footprint "RES0402")
      (description "RES SMD 124 OHM 1% 1/16W 0402")
      (fields (field (name "POWER") "0.063W, 1/16W") (field (name "TOLERANCE") "1%"))
      (libsource (lib "UWRT_Schematic_Library_2020") (part "RES_124Ω_0402_1%"))
    )
    (comp (ref "R27")
      (value "24kΩ")
      (footprint "RES0402")
      (description "RES SMD 24K OHM 1% 1/16W 0402")
      (fields (field (name "POWER") "0.063W, 1/16W") (field (name "TOLERANCE") "1%"))
      (libsource (lib "UWRT_Schematic_Library_2020") (part "RES_24kΩ_0402_1%"))
    )
    (comp (ref "R28")
      (value "7.87kΩ")
      (footprint "RES0402")
      (description "RES 7.87K OHM 1% 1/16W 0402")
      (fields (field (name "POWER") "0.063W, 1/16W") (field (name "TOLERANCE") "1%"))
      (libsource (lib "UWRT_Schematic_Library_2020") (part "RES_7.87kΩ_0402_1%"))
    )
    (comp (ref "R29")
      (value "11kΩ")
      (footprint "RES0402")
      (description "RES 11K OHM 1% 1/16W 0402")
      (fields (field (name "POWER") "0.063W, 1/16W") (field (name "TOLERANCE") "1%"))
      (libsource (lib "UWRT_Schematic_Library_2020") (part "RES_11kΩ_0402_1%"))
    )
    (comp (ref "R30")
      (value "3.48kΩ")
      (footprint "RES0402")
      (description "RES SMD 3.48K OHM 1% 1/16W 0402")
      (fields (field (name "POWER") "0.063W, 1/16W") (field (name "TOLERANCE") "1%"))
      (libsource (lib "UWRT_Schematic_Library_2020") (part "RES_3.48kΩ_0402_1%"))
    )
    (comp (ref "R31")
      (value "86.6kΩ")
      (footprint "RES0402")
      (description "RES SMD 86.6K OHM 1% 1/16W 0402")
      (fields (field (name "POWER") "0.063W, 1/16W") (field (name "TOLERANCE") "1%"))
      (libsource (lib "UWRT_Schematic_Library_2020") (part "RES_86.6kΩ_0402_1%"))
    )
    (comp (ref "R32")
      (value "4.42kΩ")
      (footprint "RES0402")
      (description "RES 4.42K OHM 1% 1/16W 0402")
      (fields (field (name "POWER") "0.063W, 1/16W") (field (name "TOLERANCE") "1%"))
      (libsource (lib "UWRT_Schematic_Library_2020") (part "RES_4.42kΩ_0402_1%"))
    )
    (comp (ref "U1")
      (value "TPS54339")
      (footprint "VREG_LM5017MR/NOPB")
      (description "IC REG BUCK ADJUSTABLE 3A 8SOPWR")
      (libsource (lib "UWRT_Schematic_Library_2020") (part "TPS54339"))
    )
    (comp (ref "U2")
      (value "LM27403SQE/NOPB")
      (footprint "QFN50P400X400X80-25N")
      (description "Buck Regulator Positive Output Step-Down - DC-DC Controller IC 24-WQFN (4x4)")
      (libsource (lib "UWRT_Schematic_Library_2020") (part "LM27403SQE/NOPB"))
    )
    (comp (ref "U3")
      (value "TPS54339")
      (footprint "VREG_LM5017MR/NOPB")
      (description "IC REG BUCK ADJUSTABLE 3A 8SOPWR")
      (libsource (lib "UWRT_Schematic_Library_2020") (part "TPS54339"))
    )
    (comp (ref "U4")
      (value "LM27403SQE/NOPB")
      (footprint "QFN50P400X400X80-25N")
      (description "Buck Regulator Positive Output Step-Down - DC-DC Controller IC 24-WQFN (4x4)")
      (libsource (lib "UWRT_Schematic_Library_2020") (part "LM27403SQE/NOPB"))
    )
  )
  (nets
    (net (code "1") (name "/CBOOT") (class "Default")
      (node (ref "C31") (pin "1") (pinfunction "1_1") (pintype "passive"))
      (node (ref "D5") (pin "1") (pintype "passive"))
      (node (ref "U4") (pin "18") (pinfunction "CBOOT_18") (pintype "passive"))
    )
    (net (code "2") (name "/SW") (class "Default")
      (node (ref "C31") (pin "2") (pinfunction "2_2") (pintype "passive"))
      (node (ref "L3") (pin "1") (pinfunction "1_1") (pintype "passive"))
      (node (ref "Q5") (pin "1") (pinfunction "Source_1") (pintype "passive"))
      (node (ref "Q6") (pin "3") (pinfunction "Drain_3") (pintype "passive"))
      (node (ref "R21") (pin "1") (pinfunction "1_1") (pintype "passive"))
      (node (ref "U4") (pin "16") (pinfunction "SW_16") (pintype "passive"))
    )
    (net (code "3") (name "/VDD") (class "Default")
      (node (ref "C45") (pin "2") (pinfunction "2_2") (pintype "passive"))
      (node (ref "C46") (pin "2") (pinfunction "2_2") (pintype "passive"))
      (node (ref "D5") (pin "2") (pintype "passive"))
      (node (ref "R24") (pin "1") (pinfunction "1_1") (pintype "passive"))
      (node (ref "U4") (pin "14") (pinfunction "VDD_14") (pintype "passive"))
    )
    (net (code "4") (name "1V2") (class "Default")
      (node (ref "C44") (pin "2") (pinfunction "2_2") (pintype "passive"))
      (node (ref "C50") (pin "2") (pinfunction "2_2") (pintype "passive"))
      (node (ref "C51") (pin "2") (pinfunction "2_2") (pintype "passive"))
      (node (ref "C52") (pin "2") (pinfunction "2_2") (pintype "passive"))
      (node (ref "L4") (pin "2") (pinfunction "2_2") (pintype "passive"))
      (node (ref "R22") (pin "2") (pinfunction "2_2") (pintype "passive"))
    )
    (net (code "5") (name "1V8") (class "Default")
      (node (ref "C14") (pin "2") (pinfunction "2_2") (pintype "passive"))
      (node (ref "C20") (pin "2") (pinfunction "2_2") (pintype "passive"))
      (node (ref "C21") (pin "2") (pinfunction "2_2") (pintype "passive"))
      (node (ref "C22") (pin "2") (pinfunction "2_2") (pintype "passive"))
      (node (ref "L2") (pin "2") (pinfunction "2_2") (pintype "passive"))
      (node (ref "R8") (pin "2") (pinfunction "2_2") (pintype "passive"))
    )
    (net (code "6") (name "3V3") (class "Default")
      (node (ref "C37") (pin "2") (pinfunction "2_2") (pintype "passive"))
      (node (ref "C38") (pin "2") (pinfunction "2_2") (pintype "passive"))
      (node (ref "C39") (pin "2") (pinfunction "2_2") (pintype "passive"))
      (node (ref "C40") (pin "2") (pinfunction "2_2") (pintype "passive"))
      (node (ref "C41") (pin "2") (pinfunction "2_2") (pintype "passive"))
      (node (ref "C43") (pin "2") (pinfunction "2_2") (pintype "passive"))
      (node (ref "L3") (pin "2") (pinfunction "2_2") (pintype "passive"))
      (node (ref "R20") (pin "2") (pinfunction "2_2") (pintype "passive"))
      (node (ref "R23") (pin "2") (pinfunction "2_2") (pintype "passive"))
      (node (ref "R28") (pin "2") (pinfunction "2_2") (pintype "passive"))
    )
    (net (code "7") (name "5V") (class "Default")
      (node (ref "C11") (pin "2") (pinfunction "2_2") (pintype "passive"))
      (node (ref "C13") (pin "2") (pinfunction "2_2") (pintype "passive"))
      (node (ref "C6") (pin "2") (pinfunction "2_2") (pintype "passive"))
      (node (ref "C7") (pin "2") (pinfunction "2_2") (pintype "passive"))
      (node (ref "C8") (pin "2") (pinfunction "2_2") (pintype "passive"))
      (node (ref "C9") (pin "2") (pinfunction "2_2") (pintype "passive"))
      (node (ref "L1") (pin "1") (pinfunction "1_1") (pintype "passive"))
      (node (ref "R13") (pin "2") (pinfunction "2_2") (pintype "passive"))
      (node (ref "R6") (pin "2") (pinfunction "2_2") (pintype "passive"))
      (node (ref "R9") (pin "2") (pinfunction "2_2") (pintype "passive"))
    )
    (net (code "8") (name "GND") (class "Default")
      (node (ref "C12") (pin "1") (pinfunction "1_1") (pintype "passive"))
      (node (ref "C15") (pin "1") (pinfunction "1_1") (pintype "passive"))
      (node (ref "C16") (pin "1") (pinfunction "1_1") (pintype "passive"))
      (node (ref "C17") (pin "1") (pinfunction "1_1") (pintype "passive"))
      (node (ref "C18") (pin "1") (pinfunction "1_1") (pintype "passive"))
      (node (ref "C19") (pin "1") (pinfunction "1_1") (pintype "passive"))
      (node (ref "C20") (pin "1") (pinfunction "1_1") (pintype "passive"))
      (node (ref "C21") (pin "1") (pinfunction "1_1") (pintype "passive"))
      (node (ref "C22") (pin "1") (pinfunction "1_1") (pintype "passive"))
      (node (ref "C23") (pin "1") (pinfunction "1_1") (pintype "passive"))
      (node (ref "C25") (pin "1") (pinfunction "1_1") (pintype "passive"))
      (node (ref "C26") (pin "1") (pinfunction "1_1") (pintype "passive"))
      (node (ref "C28") (pin "1") (pinfunction "1_1") (pintype "passive"))
      (node (ref "C3") (pin "1") (pinfunction "1_1") (pintype "passive"))
      (node (ref "C30") (pin "1") (pinfunction "1_1") (pintype "passive"))
      (node (ref "C32") (pin "1") (pinfunction "1_1") (pintype "passive"))
      (node (ref "C33") (pin "1") (pinfunction "1_1") (pintype "passive"))
      (node (ref "C34") (pin "1") (pinfunction "1_1") (pintype "passive"))
      (node (ref "C35") (pin "1") (pinfunction "1_1") (pintype "passive"))
      (node (ref "C37") (pin "1") (pinfunction "1_1") (pintype "passive"))
      (node (ref "C38") (pin "1") (pinfunction "1_1") (pintype "passive"))
      (node (ref "C39") (pin "1") (pinfunction "1_1") (pintype "passive"))
      (node (ref "C4") (pin "1") (pinfunction "1_1") (pintype "passive"))
      (node (ref "C40") (pin "1") (pinfunction "1_1") (pintype "passive"))
      (node (ref "C42") (pin "1") (pinfunction "1_1") (pintype "passive"))
      (node (ref "C45") (pin "1") (pinfunction "1_1") (pintype "passive"))
      (node (ref "C46") (pin "1") (pinfunction "1_1") (pintype "passive"))
      (node (ref "C47") (pin "1") (pinfunction "1_1") (pintype "passive"))
      (node (ref "C48") (pin "1") (pinfunction "1_1") (pintype "passive"))
      (node (ref "C49") (pin "1") (pinfunction "1_1") (pintype "passive"))
      (node (ref "C5") (pin "1") (pinfunction "1_1") (pintype "passive"))
      (node (ref "C50") (pin "1") (pinfunction "1_1") (pintype "passive"))
      (node (ref "C51") (pin "1") (pinfunction "1_1") (pintype "passive"))
      (node (ref "C52") (pin "1") (pinfunction "1_1") (pintype "passive"))
      (node (ref "C53") (pin "1") (pinfunction "1_1") (pintype "passive"))
      (node (ref "C55") (pin "1") (pinfunction "1_1") (pintype "passive"))
      (node (ref "C56") (pin "1") (pinfunction "1_1") (pintype "passive"))
      (node (ref "C58") (pin "1") (pinfunction "1_1") (pintype "passive"))
      (node (ref "C6") (pin "1") (pinfunction "1_1") (pintype "passive"))
      (node (ref "C60") (pin "1") (pinfunction "1_1") (pintype "passive"))
      (node (ref "C7") (pin "1") (pinfunction "1_1") (pintype "passive"))
      (node (ref "C8") (pin "1") (pinfunction "1_1") (pintype "passive"))
      (node (ref "C9") (pin "1") (pinfunction "1_1") (pintype "passive"))
      (node (ref "D4") (pin "2") (pinfunction "K_2") (pintype "passive"))
      (node (ref "D6") (pin "2") (pinfunction "K_2") (pintype "passive"))
      (node (ref "Q3") (pin "1") (pinfunction "Source_1") (pintype "passive"))
      (node (ref "Q4") (pin "2") (pinfunction "2_2") (pintype "passive"))
      (node (ref "Q6") (pin "1") (pinfunction "Source_1") (pintype "passive"))
      (node (ref "Q7") (pin "2") (pinfunction "2_2") (pintype "passive"))
      (node (ref "R14") (pin "1") (pinfunction "1_1") (pintype "passive"))
      (node (ref "R15") (pin "1") (pinfunction "1_1") (pintype "passive"))
      (node (ref "R17") (pin "1") (pinfunction "1_1") (pintype "passive"))
      (node (ref "R18") (pin "1") (pinfunction "1_1") (pintype "passive"))
      (node (ref "R27") (pin "1") (pinfunction "1_1") (pintype "passive"))
      (node (ref "R29") (pin "1") (pinfunction "1_1") (pintype "passive"))
      (node (ref "R31") (pin "1") (pinfunction "1_1") (pintype "passive"))
      (node (ref "R32") (pin "1") (pinfunction "1_1") (pintype "passive"))
      (node (ref "U1") (pin "4") (pinfunction "GND_4") (pintype "passive"))
      (node (ref "U1") (pin "9") (pinfunction "GND_9") (pintype "passive"))
      (node (ref "U2") (pin "10") (pinfunction "D-_10") (pintype "passive"))
      (node (ref "U2") (pin "13") (pinfunction "GND_13") (pintype "passive"))
      (node (ref "U2") (pin "2") (pinfunction "RS_2") (pintype "passive"))
      (node (ref "U2") (pin "25") (pinfunction "EP_25") (pintype "passive"))
      (node (ref "U2") (pin "6") (pinfunction "SYNC_6") (pintype "passive"))
      (node (ref "U3") (pin "4") (pinfunction "GND_4") (pintype "passive"))
      (node (ref "U3") (pin "9") (pinfunction "GND_9") (pintype "passive"))
      (node (ref "U4") (pin "10") (pinfunction "D-_10") (pintype "passive"))
      (node (ref "U4") (pin "13") (pinfunction "GND_13") (pintype "passive"))
      (node (ref "U4") (pin "2") (pinfunction "RS_2") (pintype "passive"))
      (node (ref "U4") (pin "25") (pinfunction "EP_25") (pintype "passive"))
      (node (ref "U4") (pin "6") (pinfunction "SYNC_6") (pintype "passive"))
    )
    (net (code "9") (name "Net-(C11-Pad1)") (class "Default")
      (node (ref "C11") (pin "1") (pinfunction "1_1") (pintype "passive"))
      (node (ref "R11") (pin "2") (pinfunction "2_2") (pintype "passive"))
      (node (ref "R7") (pin "2") (pinfunction "2_2") (pintype "passive"))
    )
    (net (code "10") (name "Net-(C13-Pad1)") (class "Default")
      (node (ref "C13") (pin "1") (pinfunction "1_1") (pintype "passive"))
      (node (ref "R12") (pin "2") (pinfunction "2_2") (pintype "passive"))
    )
    (net (code "11") (name "Net-(C27-Pad2)") (class "Default")
      (node (ref "C27") (pin "2") (pinfunction "2_2") (pintype "passive"))
      (node (ref "R16") (pin "1") (pinfunction "1_1") (pintype "passive"))
    )
    (net (code "12") (name "Net-(C41-Pad1)") (class "Default")
      (node (ref "C41") (pin "1") (pinfunction "1_1") (pintype "passive"))
      (node (ref "R21") (pin "2") (pinfunction "2_2") (pintype "passive"))
      (node (ref "R25") (pin "2") (pinfunction "2_2") (pintype "passive"))
    )
    (net (code "13") (name "Net-(C43-Pad1)") (class "Default")
      (node (ref "C43") (pin "1") (pinfunction "1_1") (pintype "passive"))
      (node (ref "R26") (pin "2") (pinfunction "2_2") (pintype "passive"))
    )
    (net (code "14") (name "Net-(C57-Pad2)") (class "Default")
      (node (ref "C57") (pin "2") (pinfunction "2_2") (pintype "passive"))
      (node (ref "R30") (pin "1") (pinfunction "1_1") (pintype "passive"))
    )
    (net (code "15") (name "Net-(D4-A)") (class "Default")
      (node (ref "D4") (pin "1") (pinfunction "A_1") (pintype "passive"))
      (node (ref "R6") (pin "1") (pinfunction "1_1") (pintype "passive"))
    )
    (net (code "16") (name "Net-(D6-A)") (class "Default")
      (node (ref "D6") (pin "1") (pinfunction "A_1") (pintype "passive"))
      (node (ref "R20") (pin "1") (pinfunction "1_1") (pintype "passive"))
    )
    (net (code "17") (name "Net-(Q2-Gate)") (class "Default")
      (node (ref "Q2") (pin "2") (pinfunction "Gate_2") (pintype "passive"))
      (node (ref "U2") (pin "17") (pinfunction "HG_17") (pintype "passive"))
    )
    (net (code "18") (name "Net-(Q2-Source)") (class "Default")
      (node (ref "C2") (pin "2") (pinfunction "2_2") (pintype "passive"))
      (node (ref "L1") (pin "2") (pinfunction "2_2") (pintype "passive"))
      (node (ref "Q2") (pin "1") (pinfunction "Source_1") (pintype "passive"))
      (node (ref "Q3") (pin "3") (pinfunction "Drain_3") (pintype "passive"))
      (node (ref "R7") (pin "1") (pinfunction "1_1") (pintype "passive"))
      (node (ref "U2") (pin "16") (pinfunction "SW_16") (pintype "passive"))
    )
    (net (code "19") (name "Net-(Q3-Gate)") (class "Default")
      (node (ref "Q3") (pin "2") (pinfunction "Gate_2") (pintype "passive"))
      (node (ref "U2") (pin "15") (pinfunction "LG_15") (pintype "passive"))
    )
    (net (code "20") (name "Net-(Q5-Gate)") (class "Default")
      (node (ref "Q5") (pin "2") (pinfunction "Gate_2") (pintype "passive"))
      (node (ref "U4") (pin "17") (pinfunction "HG_17") (pintype "passive"))
    )
    (net (code "21") (name "Net-(Q6-Gate)") (class "Default")
      (node (ref "Q6") (pin "2") (pinfunction "Gate_2") (pintype "passive"))
      (node (ref "U4") (pin "15") (pinfunction "LG_15") (pintype "passive"))
    )
    (net (code "22") (name "Net-(U1-SS)") (class "Default")
      (node (ref "C25") (pin "2") (pinfunction "2_2") (pintype "passive"))
      (node (ref "U1") (pin "8") (pinfunction "SS_8") (pintype "passive"))
    )
    (net (code "23") (name "Net-(U1-SW)") (class "Default")
      (node (ref "C10") (pin "2") (pinfunction "2_2") (pintype "passive"))
      (node (ref "L2") (pin "1") (pinfunction "1_1") (pintype "passive"))
      (node (ref "U1") (pin "3") (pinfunction "SW_3") (pintype "passive"))
    )
    (net (code "24") (name "Net-(U1-VBST)") (class "Default")
      (node (ref "C10") (pin "1") (pinfunction "1_1") (pintype "passive"))
      (node (ref "U1") (pin "1") (pinfunction "VBST_1") (pintype "passive"))
    )
    (net (code "25") (name "Net-(U1-VFB)") (class "Default")
      (node (ref "C14") (pin "1") (pinfunction "1_1") (pintype "passive"))
      (node (ref "R14") (pin "2") (pinfunction "2_2") (pintype "passive"))
      (node (ref "R8") (pin "1") (pinfunction "1_1") (pintype "passive"))
      (node (ref "U1") (pin "5") (pinfunction "VFB_5") (pintype "passive"))
    )
    (net (code "26") (name "Net-(U1-VREG5)") (class "Default")
      (node (ref "C23") (pin "2") (pinfunction "2_2") (pintype "passive"))
      (node (ref "U1") (pin "6") (pinfunction "VREG5_6") (pintype "passive"))
    )
    (net (code "27") (name "Net-(U2-CBOOT)") (class "Default")
      (node (ref "C2") (pin "1") (pinfunction "1_1") (pintype "passive"))
      (node (ref "D3") (pin "1") (pintype "passive"))
      (node (ref "U2") (pin "18") (pinfunction "CBOOT_18") (pintype "passive"))
    )
    (net (code "28") (name "Net-(U2-COMP)") (class "Default")
      (node (ref "C27") (pin "1") (pinfunction "1_1") (pintype "passive"))
      (node (ref "C29") (pin "1") (pinfunction "1_1") (pintype "passive"))
      (node (ref "U2") (pin "4") (pinfunction "COMP_4") (pintype "passive"))
    )
    (net (code "29") (name "Net-(U2-CS+)") (class "Default")
      (node (ref "C24") (pin "2") (pinfunction "2_2") (pintype "passive"))
      (node (ref "R11") (pin "1") (pinfunction "1_1") (pintype "passive"))
      (node (ref "U2") (pin "23") (pinfunction "CS+_23") (pintype "passive"))
    )
    (net (code "30") (name "Net-(U2-CS-)") (class "Default")
      (node (ref "C24") (pin "1") (pinfunction "1_1") (pintype "passive"))
      (node (ref "R13") (pin "1") (pinfunction "1_1") (pintype "passive"))
      (node (ref "U2") (pin "24") (pinfunction "CS-_24") (pintype "passive"))
    )
    (net (code "31") (name "Net-(U2-D+)") (class "Default")
      (node (ref "C30") (pin "2") (pinfunction "2_2") (pintype "passive"))
      (node (ref "Q4") (pin "1") (pinfunction "1_1") (pintype "passive"))
      (node (ref "Q4") (pin "3") (pinfunction "3_3") (pintype "passive"))
      (node (ref "U2") (pin "9") (pinfunction "D+_9") (pintype "passive"))
    )
    (net (code "32") (name "Net-(U2-FADJ)") (class "Default")
      (node (ref "R15") (pin "2") (pinfunction "2_2") (pintype "passive"))
      (node (ref "U2") (pin "5") (pinfunction "FADJ_5") (pintype "passive"))
    )
    (net (code "33") (name "Net-(U2-FB)") (class "Default")
      (node (ref "C29") (pin "2") (pinfunction "2_2") (pintype "passive"))
      (node (ref "R12") (pin "1") (pinfunction "1_1") (pintype "passive"))
      (node (ref "R16") (pin "2") (pinfunction "2_2") (pintype "passive"))
      (node (ref "R18") (pin "2") (pinfunction "2_2") (pintype "passive"))
      (node (ref "R9") (pin "1") (pinfunction "1_1") (pintype "passive"))
      (node (ref "U2") (pin "3") (pinfunction "FB_3") (pintype "passive"))
    )
    (net (code "34") (name "Net-(U2-OTP)") (class "Default")
      (node (ref "C28") (pin "2") (pinfunction "2_2") (pintype "passive"))
      (node (ref "R17") (pin "2") (pinfunction "2_2") (pintype "passive"))
      (node (ref "U2") (pin "8") (pinfunction "OTP_8") (pintype "passive"))
    )
    (net (code "35") (name "Net-(U2-PGOOD)") (class "Default")
      (node (ref "R10") (pin "2") (pinfunction "2_2") (pintype "passive"))
      (node (ref "U2") (pin "11") (pinfunction "PGOOD_11") (pintype "passive"))
    )
    (net (code "36") (name "Net-(U2-SS{slash}TRACK)") (class "Default")
      (node (ref "C26") (pin "2") (pinfunction "2_2") (pintype "passive"))
      (node (ref "U2") (pin "1") (pinfunction "SS/TRACK_1") (pintype "passive"))
    )
    (net (code "37") (name "Net-(U2-VDD)") (class "Default")
      (node (ref "C15") (pin "2") (pinfunction "2_2") (pintype "passive"))
      (node (ref "C16") (pin "2") (pinfunction "2_2") (pintype "passive"))
      (node (ref "D3") (pin "2") (pintype "passive"))
      (node (ref "R10") (pin "1") (pinfunction "1_1") (pintype "passive"))
      (node (ref "U2") (pin "14") (pinfunction "VDD_14") (pintype "passive"))
    )
    (net (code "38") (name "Net-(U2-VIN)") (class "Default")
      (node (ref "C12") (pin "2") (pinfunction "2_2") (pintype "passive"))
      (node (ref "R5") (pin "1") (pinfunction "1_1") (pintype "passive"))
      (node (ref "U2") (pin "12") (pinfunction "VIN_12") (pintype "passive"))
    )
    (net (code "39") (name "Net-(U3-SS)") (class "Default")
      (node (ref "C55") (pin "2") (pinfunction "2_2") (pintype "passive"))
      (node (ref "U3") (pin "8") (pinfunction "SS_8") (pintype "passive"))
    )
    (net (code "40") (name "Net-(U3-SW)") (class "Default")
      (node (ref "C36") (pin "2") (pinfunction "2_2") (pintype "passive"))
      (node (ref "L4") (pin "1") (pinfunction "1_1") (pintype "passive"))
      (node (ref "U3") (pin "3") (pinfunction "SW_3") (pintype "passive"))
    )
    (net (code "41") (name "Net-(U3-VBST)") (class "Default")
      (node (ref "C36") (pin "1") (pinfunction "1_1") (pintype "passive"))
      (node (ref "U3") (pin "1") (pinfunction "VBST_1") (pintype "passive"))
    )
    (net (code "42") (name "Net-(U3-VFB)") (class "Default")
      (node (ref "C44") (pin "1") (pinfunction "1_1") (pintype "passive"))
      (node (ref "R22") (pin "1") (pinfunction "1_1") (pintype "passive"))
      (node (ref "R27") (pin "2") (pinfunction "2_2") (pintype "passive"))
      (node (ref "U3") (pin "5") (pinfunction "VFB_5") (pintype "passive"))
    )
    (net (code "43") (name "Net-(U3-VREG5)") (class "Default")
      (node (ref "C53") (pin "2") (pinfunction "2_2") (pintype "passive"))
      (node (ref "U3") (pin "6") (pinfunction "VREG5_6") (pintype "passive"))
    )
    (net (code "44") (name "Net-(U4-COMP)") (class "Default")
      (node (ref "C57") (pin "1") (pinfunction "1_1") (pintype "passive"))
      (node (ref "C59") (pin "1") (pinfunction "1_1") (pintype "passive"))
      (node (ref "U4") (pin "4") (pinfunction "COMP_4") (pintype "passive"))
    )
    (net (code "45") (name "Net-(U4-CS+)") (class "Default")
      (node (ref "C54") (pin "2") (pinfunction "2_2") (pintype "passive"))
      (node (ref "R25") (pin "1") (pinfunction "1_1") (pintype "passive"))
      (node (ref "U4") (pin "23") (pinfunction "CS+_23") (pintype "passive"))
    )
    (net (code "46") (name "Net-(U4-CS-)") (class "Default")
      (node (ref "C54") (pin "1") (pinfunction "1_1") (pintype "passive"))
      (node (ref "R28") (pin "1") (pinfunction "1_1") (pintype "passive"))
      (node (ref "U4") (pin "24") (pinfunction "CS-_24") (pintype "passive"))
    )
    (net (code "47") (name "Net-(U4-D+)") (class "Default")
      (node (ref "C60") (pin "2") (pinfunction "2_2") (pintype "passive"))
      (node (ref "Q7") (pin "1") (pinfunction "1_1") (pintype "passive"))
      (node (ref "Q7") (pin "3") (pinfunction "3_3") (pintype "passive"))
      (node (ref "U4") (pin "9") (pinfunction "D+_9") (pintype "passive"))
    )
    (net (code "48") (name "Net-(U4-FADJ)") (class "Default")
      (node (ref "R29") (pin "2") (pinfunction "2_2") (pintype "passive"))
      (node (ref "U4") (pin "5") (pinfunction "FADJ_5") (pintype "passive"))
    )
    (net (code "49") (name "Net-(U4-FB)") (class "Default")
      (node (ref "C59") (pin "2") (pinfunction "2_2") (pintype "passive"))
      (node (ref "R23") (pin "1") (pinfunction "1_1") (pintype "passive"))
      (node (ref "R26") (pin "1") (pinfunction "1_1") (pintype "passive"))
      (node (ref "R30") (pin "2") (pinfunction "2_2") (pintype "passive"))
      (node (ref "R32") (pin "2") (pinfunction "2_2") (pintype "passive"))
      (node (ref "U4") (pin "3") (pinfunction "FB_3") (pintype "passive"))
    )
    (net (code "50") (name "Net-(U4-OTP)") (class "Default")
      (node (ref "C58") (pin "2") (pinfunction "2_2") (pintype "passive"))
      (node (ref "R31") (pin "2") (pinfunction "2_2") (pintype "passive"))
      (node (ref "U4") (pin "8") (pinfunction "OTP_8") (pintype "passive"))
    )
    (net (code "51") (name "Net-(U4-PGOOD)") (class "Default")
      (node (ref "R24") (pin "2") (pinfunction "2_2") (pintype "passive"))
      (node (ref "U4") (pin "11") (pinfunction "PGOOD_11") (pintype "passive"))
    )
    (net (code "52") (name "Net-(U4-SS{slash}TRACK)") (class "Default")
      (node (ref "C56") (pin "2") (pinfunction "2_2") (pintype "passive"))
      (node (ref "U4") (pin "1") (pinfunction "SS/TRACK_1") (pintype "passive"))
    )
    (net (code "53") (name "Net-(U4-VIN)") (class "Default")
      (node (ref "C42") (pin "2") (pinfunction "2_2") (pintype "passive"))
      (node (ref "R19") (pin "1") (pinfunction "1_1") (pintype "passive"))
      (node (ref "U4") (pin "12") (pinfunction "VIN_12") (pintype "passive"))
    )
    (net (code "54") (name "VBAT") (class "Default")
      (node (ref "C17") (pin "2") (pinfunction "2_2") (pintype "passive"))
      (node (ref "C18") (pin "2") (pinfunction "2_2") (pintype "passive"))
      (node (ref "C19") (pin "2") (pinfunction "2_2") (pintype "passive"))
      (node (ref "C3") (pin "2") (pinfunction "2_2") (pintype "passive"))
      (node (ref "C32") (pin "2") (pinfunction "2_2") (pintype "passive"))
      (node (ref "C33") (pin "2") (pinfunction "2_2") (pintype "passive"))
      (node (ref "C34") (pin "2") (pinfunction "2_2") (pintype "passive"))
      (node (ref "C35") (pin "2") (pinfunction "2_2") (pintype "passive"))
      (node (ref "C4") (pin "2") (pinfunction "2_2") (pintype "passive"))
      (node (ref "C47") (pin "2") (pinfunction "2_2") (pintype "passive"))
      (node (ref "C48") (pin "2") (pinfunction "2_2") (pintype "passive"))
      (node (ref "C49") (pin "2") (pinfunction "2_2") (pintype "passive"))
      (node (ref "C5") (pin "2") (pinfunction "2_2") (pintype "passive"))
      (node (ref "Q2") (pin "3") (pinfunction "Drain_3") (pintype "passive"))
      (node (ref "Q5") (pin "3") (pinfunction "Drain_3") (pintype "passive"))
      (node (ref "R19") (pin "2") (pinfunction "2_2") (pintype "passive"))
      (node (ref "R5") (pin "2") (pinfunction "2_2") (pintype "passive"))
      (node (ref "U1") (pin "2") (pinfunction "VIN_2") (pintype "passive"))
      (node (ref "U1") (pin "7") (pinfunction "EN_7") (pintype "passive"))
      (node (ref "U3") (pin "2") (pinfunction "VIN_2") (pintype "passive"))
      (node (ref "U3") (pin "7") (pinfunction "EN_7") (pintype "passive"))
    )
    (net (code "55") (name "unconnected-(U2-UVLO{slash}EN-Pad7)") (class "Default")
      (node (ref "U2") (pin "7") (pinfunction "UVLO/EN_7") (pintype "passive+no_connect"))
    )
    (net (code "56") (name "unconnected-(U4-UVLO{slash}EN-Pad7)") (class "Default")
      (node (ref "U4") (pin "7") (pinfunction "UVLO/EN_7") (pintype "passive+no_connect"))
    )
  )
)
